# Mesure.net
KiCad netlist of a schematic drawn in Altium Designer
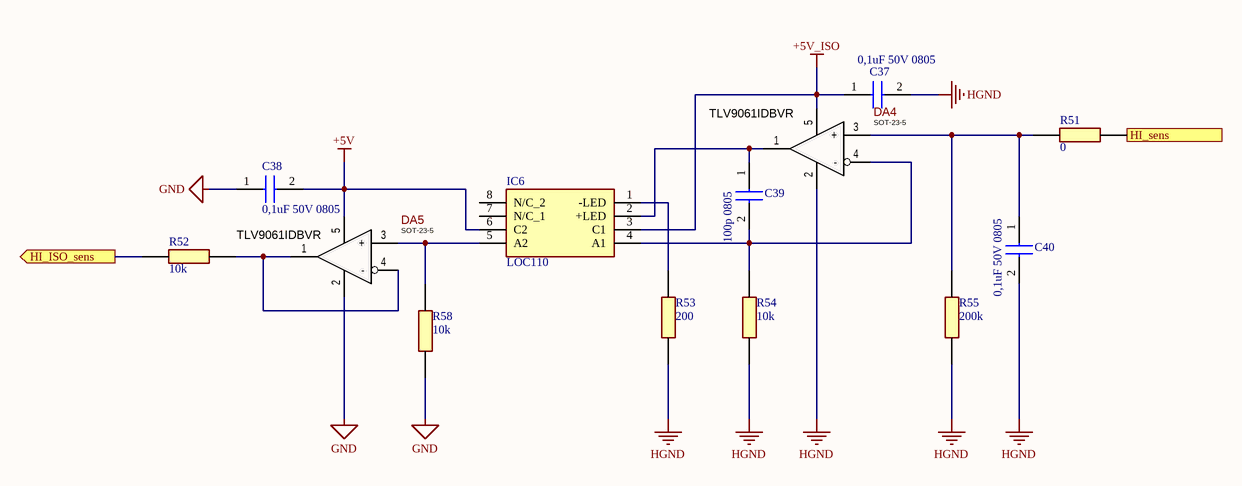
[diagram p0: Mesure.SchDoc]

(export (version "E")
  (design (tool "Eeschema 10.0.6"))
  (components
    (comp (ref "C37")
      (value "0,1uF 50V 0805")
      (footprint "SamacSys:CAPC2012X90N")
      (description "Capacitor")
      (libsource (lib "*") (part "MCMT21N470F250CT"))
    )
    (comp (ref "C38")
      (value "0,1uF 50V 0805")
      (footprint "SamacSys:CAPC2012X90N")
      (description "Capacitor")
      (libsource (lib "*") (part "MCMT21N470F250CT"))
    )
    (comp (ref "C39")
      (value "100p 0805")
      (footprint "SamacSys:CAPC2012X90N")
      (description "Capacitor")
      (libsource (lib "*") (part "MCMT21N470F250CT"))
    )
    (comp (ref "C40")
      (value "0,1uF 50V 0805")
      (footprint "SamacSys:CAPC2012X90N")
      (description "Capacitor")
      (libsource (lib "*") (part "MCMT21N470F250CT"))
    )
    (comp (ref "DA4")
      (value "TLV9061IDBVR")
      (footprint "SOT-23-5")
      (fields
        (field (name "PACKAGE") "SOT-23-5")
        (field (name "PART NUMBER") "TLV9061IDBVR")
        (field (name "MANUFACTURER") "Texas Instruments")
      )
      (libsource (lib "AjaxLibrary") (part "TLV90x1IDBVR"))
    )
    (comp (ref "DA5")
      (value "TLV9061IDBVR")
      (footprint "SOT-23-5")
      (fields
        (field (name "PACKAGE") "SOT-23-5")
        (field (name "PART NUMBER") "TLV9061IDBVR")
        (field (name "MANUFACTURER") "Texas Instruments")
      )
      (libsource (lib "AjaxLibrary") (part "TLV90x1IDBVR"))
    )
    (comp (ref "IC6")
      (value "LOC110")
      (footprint "SamacSys:DIP762W53P254L965H335Q8N")
      (description "Integrated Circuit")
      (fields (field (name "MOUSER PART NUMBER") "849-LOC110"))
      (libsource (lib "SamacSys") (part "LOC110"))
    )
    (comp (ref "R51")
      (value "0")
      (footprint "RESC2013X65N")
      (description "Resistor")
      (libsource (lib "") (part "ERJP06J822V_1"))
    )
    (comp (ref "R52")
      (value "10k")
      (footprint "RESC2013X65N")
      (description "Resistor")
      (libsource (lib "") (part "ERJP06J822V_1"))
    )
    (comp (ref "R53")
      (value "200")
      (footprint "RESC2013X65N")
      (description "Resistor")
      (libsource (lib "SamacSys") (part "ERJP06J822V"))
    )
    (comp (ref "R54")
      (value "10k")
      (footprint "RESC2013X65N")
      (description "Resistor")
      (libsource (lib "SamacSys") (part "ERJP06J822V"))
    )
    (comp (ref "R55")
      (value "200k")
      (footprint "RESC2013X65N")
      (description "Resistor")
      (libsource (lib "SamacSys") (part "ERJP06J822V"))
    )
    (comp (ref "R58")
      (value "10k")
      (footprint "RESC2013X65N")
      (description "Resistor")
      (libsource (lib "SamacSys") (part "ERJP06J822V"))
    )
  )
  (nets
    (net (code "1") (name "+5V") (class "Default")
      (node (ref "C38") (pin "2") (pinfunction "2_2") (pintype "passive"))
      (node (ref "DA5") (pin "5") (pinfunction "V+_5") (pintype "passive"))
      (node (ref "IC6") (pin "6") (pinfunction "C2_6") (pintype "passive"))
    )
    (net (code "2") (name "+5V_ISO") (class "Default")
      (node (ref "C37") (pin "1") (pinfunction "1_1") (pintype "passive"))
      (node (ref "DA4") (pin "5") (pinfunction "V+_5") (pintype "passive"))
      (node (ref "IC6") (pin "3") (pinfunction "C1_3") (pintype "passive"))
    )
    (net (code "3") (name "/HI_ISO_sens") (class "Default")
      (node (ref "R52") (pin "2") (pinfunction "2_2") (pintype "passive"))
    )
    (net (code "4") (name "/HI_sens") (class "Default")
      (node (ref "R51") (pin "1") (pinfunction "1_1") (pintype "passive"))
    )
    (net (code "5") (name "GND") (class "Default")
      (node (ref "C38") (pin "1") (pinfunction "1_1") (pintype "passive"))
      (node (ref "DA5") (pin "2") (pinfunction "V-_2") (pintype "passive"))
      (node (ref "R58") (pin "1") (pinfunction "1_1") (pintype "passive"))
    )
    (net (code "6") (name "HGND") (class "Default")
      (node (ref "C37") (pin "2") (pinfunction "2_2") (pintype "passive"))
      (node (ref "C40") (pin "2") (pinfunction "2_2") (pintype "passive"))
      (node (ref "DA4") (pin "2") (pinfunction "V-_2") (pintype "passive"))
      (node (ref "R53") (pin "1") (pinfunction "1_1") (pintype "passive"))
      (node (ref "R54") (pin "1") (pinfunction "1_1") (pintype "passive"))
      (node (ref "R55") (pin "1") (pinfunction "1_1") (pintype "passive"))
    )
    (net (code "7") (name "Net-(DA4-+)") (class "Default")
      (node (ref "C40") (pin "1") (pinfunction "1_1") (pintype "passive"))
      (node (ref "DA4") (pin "3") (pinfunction "+_3") (pintype "passive"))
      (node (ref "R51") (pin "2") (pinfunction "2_2") (pintype "passive"))
      (node (ref "R55") (pin "2") (pinfunction "2_2") (pintype "passive"))
    )
    (net (code "8") (name "Net-(DA4--)") (class "Default")
      (node (ref "C39") (pin "2") (pinfunction "2_2") (pintype "passive"))
      (node (ref "DA4") (pin "4") (pinfunction "-_4") (pintype "passive"))
      (node (ref "IC6") (pin "4") (pinfunction "A1_4") (pintype "passive"))
      (node (ref "R54") (pin "2") (pinfunction "2_2") (pintype "passive"))
    )
    (net (code "9") (name "Net-(DA4-OUT)") (class "Default")
      (node (ref "C39") (pin "1") (pinfunction "1_1") (pintype "passive"))
      (node (ref "DA4") (pin "1") (pinfunction "OUT_1") (pintype "passive"))
      (node (ref "IC6") (pin "2") (pinfunction "+LED_2") (pintype "passive"))
    )
    (net (code "10") (name "Net-(DA5-+)") (class "Default")
      (node (ref "DA5") (pin "3") (pinfunction "+_3") (pintype "passive"))
      (node (ref "IC6") (pin "5") (pinfunction "A2_5") (pintype "passive"))
      (node (ref "R58") (pin "2") (pinfunction "2_2") (pintype "passive"))
    )
    (net (code "11") (name "Net-(DA5--)") (class "Default")
      (node (ref "DA5") (pin "1") (pinfunction "OUT_1") (pintype "passive"))
      (node (ref "DA5") (pin "4") (pinfunction "-_4") (pintype "passive"))
      (node (ref "R52") (pin "1") (pinfunction "1_1") (pintype "passive"))
    )
    (net (code "12") (name "Net-(IC6--LED)") (class "Default")
      (node (ref "IC6") (pin "1") (pinfunction "-LED_1") (pintype "passive"))
      (node (ref "R53") (pin "2") (pinfunction "2_2") (pintype "passive"))
    )
    (net (code "13") (name "unconnected-(IC6-N{slash}C_1-Pad7)") (class "Default")
      (node (ref "IC6") (pin "7") (pinfunction "N/C_1_7") (pintype "passive"))
    )
    (net (code "14") (name "unconnected-(IC6-N{slash}C_2-Pad8)") (class "Default")
      (node (ref "IC6") (pin "8") (pinfunction "N/C_2_8") (pintype "passive"))
    )
  )
)
